# Temperature.net
KiCad netlist of a schematic drawn in Altium Designer
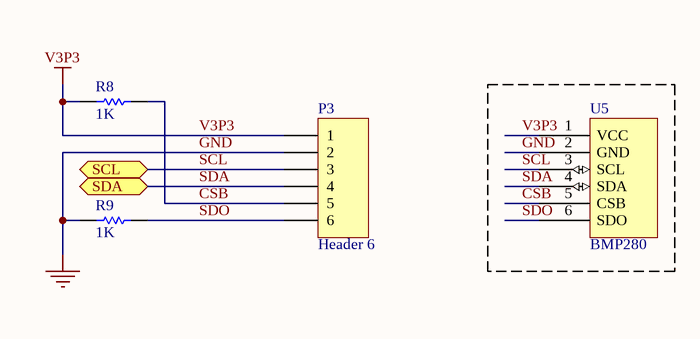
[diagram p0: Temperature.SchDoc]

(export (version "E")
  (design (tool "Eeschema 10.0.6"))
  (components
    (comp (ref "P3")
      (value "Header 6")
      (footprint "Header 6")
      (description "Header, 6-Pin")
      (libsource (lib "Miscellaneous Connectors") (part "Header 6"))
    )
    (comp (ref "R8")
      (value "1K")
      (footprint "RES0603")
      (description "Resistor")
      (fields (field (name "PUBLISHER") "Altium Limited"))
      (libsource (lib "Miscellaneous Devices") (part "Res1"))
    )
    (comp (ref "R9")
      (value "1K")
      (footprint "RES0603")
      (description "Resistor")
      (fields (field (name "PUBLISHER") "Altium Limited"))
      (libsource (lib "Miscellaneous Devices") (part "Res1"))
    )
    (comp (ref "U5")
      (value "BMP280")
      (description "Temp. sensor")
      (libsource (lib "Components") (part "BMP280"))
    )
  )
  (nets
    (net (code "1") (name "/CSB") (class "Default")
      (node (ref "P3") (pin "5") (pinfunction "5_5") (pintype "passive"))
      (node (ref "R8") (pin "2") (pinfunction "2_2") (pintype "passive"))
      (node (ref "U5") (pin "5") (pinfunction "CSB_5") (pintype "passive"))
    )
    (net (code "2") (name "/SCL") (class "Default")
      (node (ref "P3") (pin "3") (pinfunction "3_3") (pintype "passive"))
      (node (ref "U5") (pin "3") (pinfunction "SCL_3") (pintype "bidirectional"))
    )
    (net (code "3") (name "/SDA") (class "Default")
      (node (ref "P3") (pin "4") (pinfunction "4_4") (pintype "passive"))
      (node (ref "U5") (pin "4") (pinfunction "SDA_4") (pintype "bidirectional"))
    )
    (net (code "4") (name "/SDO") (class "Default")
      (node (ref "P3") (pin "6") (pinfunction "6_6") (pintype "passive"))
      (node (ref "R9") (pin "2") (pinfunction "2_2") (pintype "passive"))
      (node (ref "U5") (pin "6") (pinfunction "SDO_6") (pintype "passive"))
    )
    (net (code "5") (name "GND") (class "Default")
      (node (ref "P3") (pin "2") (pinfunction "2_2") (pintype "power_in"))
      (node (ref "R9") (pin "1") (pinfunction "1_1") (pintype "passive"))
      (node (ref "U5") (pin "2") (pinfunction "GND_2") (pintype "power_in"))
    )
    (net (code "6") (name "V3P3") (class "Default")
      (node (ref "P3") (pin "1") (pinfunction "1_1") (pintype "power_in"))
      (node (ref "R8") (pin "1") (pinfunction "1_1") (pintype "passive"))
      (node (ref "U5") (pin "1") (pinfunction "VCC_1") (pintype "power_in"))
    )
  )
)
